# SCH_NIRV2_1_NOMOSFET-REG.net
KiCad netlist of a schematic drawn in EasyEDA
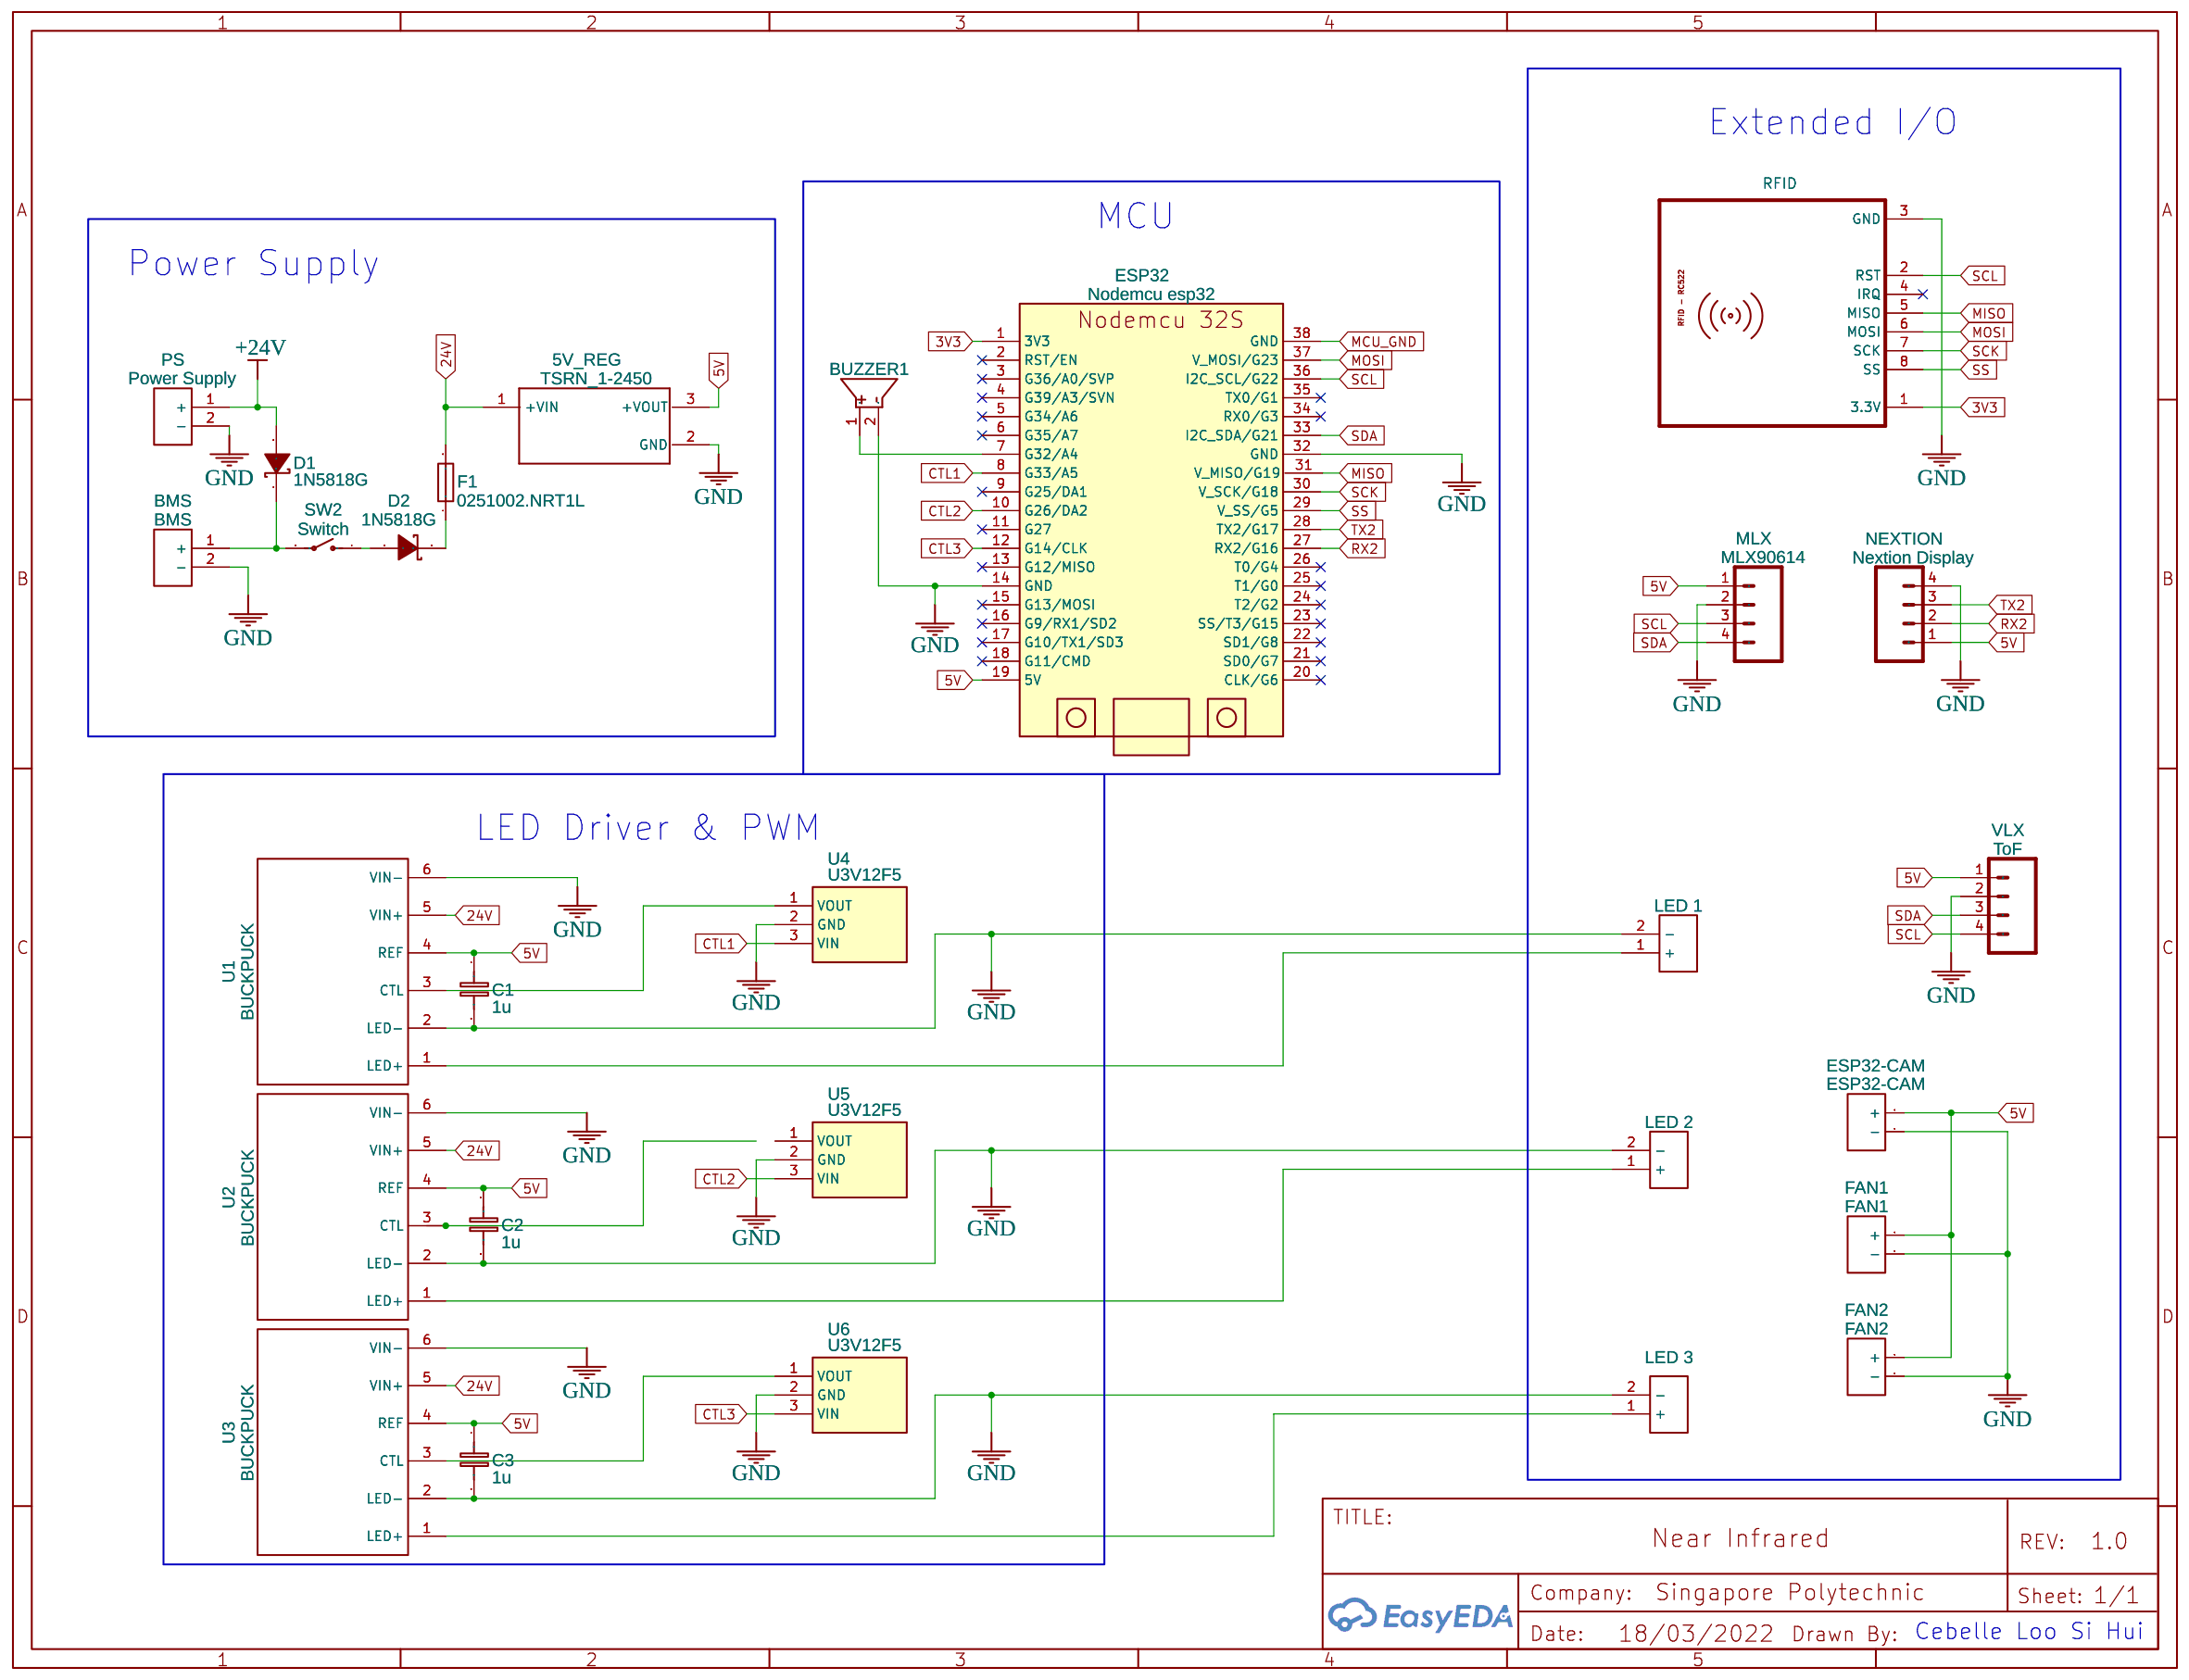
[diagram p0: schematic sheet]

(export (version "E")
  (design (tool "Eeschema 10.0.6"))
  (components
    (comp (ref "5V_REG") (value "TSRN_1-2450") (libsource (lib "") (part "TSRN_1-2450")))
    (comp (ref "BMS")
      (value "BMS")
      (fields
        (field (name "BOM_Manufacturer Part") "WJ103-5.00-2P")
        (field (name "BOM_Supplier Part") "C8439")
      )
      (libsource (lib "") (part "WJ103-5.00-2P_1"))
    )
    (comp (ref "BUZZER1")
      (value "FMQ-BUZZER2")
      (fields (field (name "BOM_Supplier Part") "C9900006103"))
      (libsource (lib "") (part "FMQ-BUZZER2"))
    )
    (comp (ref "C1") (value "1u") (libsource (lib "") (part "CAP-C")))
    (comp (ref "C2") (value "1u") (libsource (lib "") (part "CAP-C")))
    (comp (ref "C3") (value "1u") (libsource (lib "") (part "CAP-C_1")))
    (comp (ref "D1")
      (value "1N5818G")
      (fields (field (name "BOM_Supplier Part") "C232462"))
      (libsource (lib "") (part "1N5818G"))
    )
    (comp (ref "D2")
      (value "1N5818G")
      (fields (field (name "BOM_Supplier Part") "C232462"))
      (libsource (lib "") (part "1N5818G_1"))
    )
    (comp (ref "ESP32") (value "Nodemcu esp32") (libsource (lib "") (part "Nodemcu esp32")))
    (comp (ref "ESP32-CAM")
      (value "ESP32-CAM")
      (fields
        (field (name "BOM_Manufacturer Part") "2.54-1*2PFemale")
        (field (name "BOM_Supplier Part") "C49661")
      )
      (libsource (lib "") (part "Header-Female-2.54_1x2_1"))
    )
    (comp (ref "F1")
      (value "0251002.NRT1L")
      (fields (field (name "BOM_Supplier Part") "C151088"))
      (libsource (lib "") (part "0251002.NRT1L"))
    )
    (comp (ref "FAN1")
      (value "FAN1")
      (fields
        (field (name "BOM_Manufacturer Part") "2.54-1*2PFemale")
        (field (name "BOM_Supplier Part") "C49661")
      )
      (libsource (lib "") (part "Header-Female-2.54_1x2"))
    )
    (comp (ref "FAN2")
      (value "FAN2")
      (fields
        (field (name "BOM_Manufacturer Part") "2.54-1*2PFemale")
        (field (name "BOM_Supplier Part") "C49661")
      )
      (libsource (lib "") (part "Header-Female-2.54_1x2"))
    )
    (comp (ref "LED4")
      (value "LED 1")
      (fields
        (field (name "BOM_Manufacturer Part") "WJ103-5.00-2P")
        (field (name "BOM_Supplier Part") "C8439")
      )
      (libsource (lib "") (part "WJ103-5.00-2P"))
    )
    (comp (ref "LED5")
      (value "LED 2")
      (fields
        (field (name "BOM_Manufacturer Part") "WJ103-5.00-2P")
        (field (name "BOM_Supplier Part") "C8439")
      )
      (libsource (lib "") (part "WJ103-5.00-2P"))
    )
    (comp (ref "LED6")
      (value "LED 3")
      (fields
        (field (name "BOM_Manufacturer Part") "WJ103-5.00-2P")
        (field (name "BOM_Supplier Part") "C8439")
      )
      (libsource (lib "") (part "WJ103-5.00-2P"))
    )
    (comp (ref "MLX") (value "MLX90614") (libsource (lib "") (part "M04POLAR")))
    (comp (ref "NEXTION") (value "Nextion Display") (libsource (lib "") (part "M04POLAR_2")))
    (comp (ref "PS")
      (value "Power Supply")
      (fields
        (field (name "BOM_Manufacturer Part") "WJ103-5.00-2P")
        (field (name "BOM_Supplier Part") "C8439")
      )
      (libsource (lib "") (part "WJ103-5.00-2P_2"))
    )
    (comp (ref "RFID") (value "NO") (libsource (lib "") (part "Unknown_944_-720")))
    (comp (ref "SW2")
      (value "Switch")
      (fields (field (name "BOM_Manufacturer Part") "KCD1-11-1.5x1cm"))
      (libsource (lib "") (part "SWITCH-2P-SPST-Rocker-10x15mm"))
    )
    (comp (ref "U1") (value "BUCKPUCK") (libsource (lib "") (part "BUCKPUCK")))
    (comp (ref "U2") (value "BUCKPUCK") (libsource (lib "") (part "BUCKPUCK")))
    (comp (ref "U3") (value "BUCKPUCK") (libsource (lib "") (part "BUCKPUCK")))
    (comp (ref "U4") (value "U3V12F5") (libsource (lib "") (part "U3V12F5")))
    (comp (ref "U5") (value "U3V12F5") (libsource (lib "") (part "U3V12F5")))
    (comp (ref "U6") (value "U3V12F5") (libsource (lib "") (part "U3V12F5")))
    (comp (ref "VLX") (value "ToF") (libsource (lib "") (part "M04POLAR_1")))
  )
  (nets
    (net (code "1") (name "+24V") (class "Default")
      (node (ref "D1") (pin "2") (pinfunction "A_2") (pintype "unspecified"))
      (node (ref "PS") (pin "1") (pinfunction "+_1") (pintype "unspecified"))
    )
    (net (code "2") (name "3V3") (class "Default")
      (node (ref "ESP32") (pin "1") (pinfunction "3V3_1") (pintype "passive"))
      (node (ref "RFID") (pin "1") (pinfunction "3.3V_1") (pintype "unspecified"))
    )
    (net (code "3") (name "5V") (class "Default")
      (node (ref "5V_REG") (pin "3") (pinfunction "+VOUT_3") (pintype "bidirectional"))
      (node (ref "C1") (pin "1") (pinfunction "1_1") (pintype "unspecified"))
      (node (ref "C2") (pin "1") (pinfunction "1_1") (pintype "unspecified"))
      (node (ref "C3") (pin "1") (pinfunction "1_1") (pintype "unspecified"))
      (node (ref "ESP32") (pin "19") (pinfunction "5V_19") (pintype "passive"))
      (node (ref "ESP32-CAM") (pin "2") (pinfunction "+_2") (pintype "input"))
      (node (ref "FAN1") (pin "2") (pinfunction "+_2") (pintype "input"))
      (node (ref "FAN2") (pin "2") (pinfunction "+_2") (pintype "input"))
      (node (ref "MLX") (pin "1") (pinfunction "GND_1") (pintype "unspecified"))
      (node (ref "NEXTION") (pin "1") (pinfunction "GND_1") (pintype "unspecified"))
      (node (ref "U1") (pin "4") (pinfunction "REF_4") (pintype "unspecified"))
      (node (ref "U2") (pin "4") (pinfunction "REF_4") (pintype "unspecified"))
      (node (ref "U3") (pin "4") (pinfunction "REF_4") (pintype "unspecified"))
      (node (ref "VLX") (pin "1") (pinfunction "GND_1") (pintype "unspecified"))
    )
    (net (code "4") (name "24V") (class "Default")
      (node (ref "5V_REG") (pin "1") (pinfunction "+VIN_1") (pintype "bidirectional"))
      (node (ref "F1") (pin "2") (pinfunction "2_2") (pintype "unspecified"))
      (node (ref "U1") (pin "5") (pinfunction "VIN+_5") (pintype "unspecified"))
      (node (ref "U2") (pin "5") (pinfunction "VIN+_5") (pintype "unspecified"))
      (node (ref "U3") (pin "5") (pinfunction "VIN+_5") (pintype "unspecified"))
    )
    (net (code "5") (name "CTL1") (class "Default")
      (node (ref "ESP32") (pin "8") (pinfunction "G33/A5_8") (pintype "bidirectional"))
      (node (ref "U4") (pin "3") (pinfunction "VIN_3") (pintype "unspecified"))
    )
    (net (code "6") (name "CTL2") (class "Default")
      (node (ref "ESP32") (pin "10") (pinfunction "G26/DA2_10") (pintype "bidirectional"))
      (node (ref "U5") (pin "3") (pinfunction "VIN_3") (pintype "unspecified"))
    )
    (net (code "7") (name "CTL3") (class "Default")
      (node (ref "ESP32") (pin "12") (pinfunction "G14/CLK_12") (pintype "bidirectional"))
      (node (ref "U6") (pin "3") (pinfunction "VIN_3") (pintype "unspecified"))
    )
    (net (code "8") (name "GND") (class "Default")
      (node (ref "5V_REG") (pin "2") (pinfunction "GND_2") (pintype "bidirectional"))
      (node (ref "BMS") (pin "2") (pinfunction "-_2") (pintype "unspecified"))
      (node (ref "BUZZER1") (pin "2") (pinfunction "2_2") (pintype "unspecified"))
      (node (ref "C1") (pin "2") (pinfunction "2_2") (pintype "unspecified"))
      (node (ref "C2") (pin "2") (pinfunction "2_2") (pintype "unspecified"))
      (node (ref "C3") (pin "2") (pinfunction "2_2") (pintype "unspecified"))
      (node (ref "ESP32") (pin "14") (pinfunction "GND_14") (pintype "passive"))
      (node (ref "ESP32") (pin "32") (pinfunction "GND_32") (pintype "passive"))
      (node (ref "ESP32-CAM") (pin "1") (pinfunction "-_1") (pintype "input"))
      (node (ref "FAN1") (pin "1") (pinfunction "-_1") (pintype "input"))
      (node (ref "FAN2") (pin "1") (pinfunction "-_1") (pintype "input"))
      (node (ref "LED4") (pin "2") (pinfunction "-_2") (pintype "unspecified"))
      (node (ref "LED5") (pin "2") (pinfunction "-_2") (pintype "unspecified"))
      (node (ref "LED6") (pin "2") (pinfunction "-_2") (pintype "unspecified"))
      (node (ref "MLX") (pin "2") (pinfunction "RX_2") (pintype "unspecified"))
      (node (ref "NEXTION") (pin "4") (pinfunction "+5V_4") (pintype "unspecified"))
      (node (ref "PS") (pin "2") (pinfunction "-_2") (pintype "unspecified"))
      (node (ref "RFID") (pin "3") (pinfunction "GND_3") (pintype "unspecified"))
      (node (ref "U1") (pin "2") (pinfunction "LED-_2") (pintype "unspecified"))
      (node (ref "U1") (pin "6") (pinfunction "VIN-_6") (pintype "unspecified"))
      (node (ref "U2") (pin "2") (pinfunction "LED-_2") (pintype "unspecified"))
      (node (ref "U2") (pin "6") (pinfunction "VIN-_6") (pintype "unspecified"))
      (node (ref "U3") (pin "2") (pinfunction "LED-_2") (pintype "unspecified"))
      (node (ref "U3") (pin "6") (pinfunction "VIN-_6") (pintype "unspecified"))
      (node (ref "U4") (pin "2") (pinfunction "GND_2") (pintype "unspecified"))
      (node (ref "U5") (pin "2") (pinfunction "GND_2") (pintype "unspecified"))
      (node (ref "U6") (pin "2") (pinfunction "GND_2") (pintype "unspecified"))
      (node (ref "VLX") (pin "2") (pinfunction "RX_2") (pintype "unspecified"))
    )
    (net (code "9") (name "MCU_GND") (class "Default")
      (node (ref "ESP32") (pin "38") (pinfunction "GND_38") (pintype "passive"))
    )
    (net (code "10") (name "MISO") (class "Default")
      (node (ref "ESP32") (pin "31") (pinfunction "V_MISO/G19_31") (pintype "bidirectional"))
      (node (ref "RFID") (pin "5") (pinfunction "MISO_5") (pintype "unspecified"))
    )
    (net (code "11") (name "MOSI") (class "Default")
      (node (ref "ESP32") (pin "37") (pinfunction "V_MOSI/G23_37") (pintype "bidirectional"))
      (node (ref "RFID") (pin "6") (pinfunction "MOSI_6") (pintype "unspecified"))
    )
    (net (code "12") (name "Net-(BMS-+)") (class "Default")
      (node (ref "BMS") (pin "1") (pinfunction "+_1") (pintype "unspecified"))
      (node (ref "D1") (pin "1") (pinfunction "C_1") (pintype "unspecified"))
      (node (ref "SW2") (pin "2") (pinfunction "P_2") (pintype "unspecified"))
    )
    (net (code "13") (name "Net-(D2-A)") (class "Default")
      (node (ref "D2") (pin "2") (pinfunction "A_2") (pintype "unspecified"))
      (node (ref "SW2") (pin "1") (pinfunction "O_1") (pintype "unspecified"))
    )
    (net (code "14") (name "Net-(D2-C)") (class "Default")
      (node (ref "D2") (pin "1") (pinfunction "C_1") (pintype "unspecified"))
      (node (ref "F1") (pin "1") (pinfunction "1_1") (pintype "unspecified"))
    )
    (net (code "15") (name "Net-(ESP32-G32{slash}A4)") (class "Default")
      (node (ref "BUZZER1") (pin "1") (pinfunction "1_1") (pintype "unspecified"))
      (node (ref "ESP32") (pin "7") (pinfunction "G32/A4_7") (pintype "bidirectional"))
    )
    (net (code "16") (name "Net-(LED4-+)") (class "Default")
      (node (ref "LED4") (pin "1") (pinfunction "+_1") (pintype "unspecified"))
      (node (ref "U1") (pin "1") (pinfunction "LED+_1") (pintype "unspecified"))
    )
    (net (code "17") (name "Net-(LED5-+)") (class "Default")
      (node (ref "LED5") (pin "1") (pinfunction "+_1") (pintype "unspecified"))
      (node (ref "U2") (pin "1") (pinfunction "LED+_1") (pintype "unspecified"))
    )
    (net (code "18") (name "Net-(LED6-+)") (class "Default")
      (node (ref "LED6") (pin "1") (pinfunction "+_1") (pintype "unspecified"))
      (node (ref "U3") (pin "1") (pinfunction "LED+_1") (pintype "unspecified"))
    )
    (net (code "19") (name "Net-(U1-CTL)") (class "Default")
      (node (ref "U1") (pin "3") (pinfunction "CTL_3") (pintype "unspecified"))
      (node (ref "U4") (pin "1") (pinfunction "VOUT_1") (pintype "unspecified"))
    )
    (net (code "20") (name "Net-(U3-CTL)") (class "Default")
      (node (ref "U3") (pin "3") (pinfunction "CTL_3") (pintype "unspecified"))
      (node (ref "U6") (pin "1") (pinfunction "VOUT_1") (pintype "unspecified"))
    )
    (net (code "21") (name "RX2") (class "Default")
      (node (ref "ESP32") (pin "27") (pinfunction "RX2/G16_27") (pintype "bidirectional"))
      (node (ref "NEXTION") (pin "2") (pinfunction "RX_2") (pintype "unspecified"))
    )
    (net (code "22") (name "SCK") (class "Default")
      (node (ref "ESP32") (pin "30") (pinfunction "V_SCK/G18_30") (pintype "bidirectional"))
      (node (ref "RFID") (pin "7") (pinfunction "SCK_7") (pintype "unspecified"))
    )
    (net (code "23") (name "SCL") (class "Default")
      (node (ref "ESP32") (pin "36") (pinfunction "I2C_SCL/G22_36") (pintype "bidirectional"))
      (node (ref "MLX") (pin "3") (pinfunction "TX_3") (pintype "unspecified"))
      (node (ref "RFID") (pin "2") (pinfunction "RST_2") (pintype "unspecified"))
      (node (ref "VLX") (pin "4") (pinfunction "+5V_4") (pintype "unspecified"))
    )
    (net (code "24") (name "SDA") (class "Default")
      (node (ref "ESP32") (pin "33") (pinfunction "I2C_SDA/G21_33") (pintype "bidirectional"))
      (node (ref "MLX") (pin "4") (pinfunction "+5V_4") (pintype "unspecified"))
      (node (ref "VLX") (pin "3") (pinfunction "TX_3") (pintype "unspecified"))
    )
    (net (code "25") (name "SS") (class "Default")
      (node (ref "ESP32") (pin "29") (pinfunction "V_SS/G5_29") (pintype "bidirectional"))
      (node (ref "RFID") (pin "8") (pinfunction "SS_8") (pintype "unspecified"))
    )
    (net (code "26") (name "TX2") (class "Default")
      (node (ref "ESP32") (pin "28") (pinfunction "TX2/G17_28") (pintype "bidirectional"))
      (node (ref "NEXTION") (pin "3") (pinfunction "TX_3") (pintype "unspecified"))
    )
    (net (code "27") (name "unconnected-(ESP32-CLK{slash}G6-Pad20)") (class "Default")
      (node (ref "ESP32") (pin "20") (pinfunction "CLK/G6_20") (pintype "bidirectional+no_connect"))
    )
    (net (code "28") (name "unconnected-(ESP32-G9{slash}RX1{slash}SD2-Pad16)") (class "Default")
      (node (ref "ESP32") (pin "16") (pinfunction "G9/RX1/SD2_16") (pintype "bidirectional+no_connect"))
    )
    (net (code "29") (name "unconnected-(ESP32-G10{slash}TX1{slash}SD3-Pad17)") (class "Default")
      (node (ref "ESP32") (pin "17") (pinfunction "G10/TX1/SD3_17") (pintype "bidirectional+no_connect"))
    )
    (net (code "30") (name "unconnected-(ESP32-G11{slash}CMD-Pad18)") (class "Default")
      (node (ref "ESP32") (pin "18") (pinfunction "G11/CMD_18") (pintype "bidirectional+no_connect"))
    )
    (net (code "31") (name "unconnected-(ESP32-G12{slash}MISO-Pad13)") (class "Default")
      (node (ref "ESP32") (pin "13") (pinfunction "G12/MISO_13") (pintype "bidirectional+no_connect"))
    )
    (net (code "32") (name "unconnected-(ESP32-G13{slash}MOSI-Pad15)") (class "Default")
      (node (ref "ESP32") (pin "15") (pinfunction "G13/MOSI_15") (pintype "bidirectional+no_connect"))
    )
    (net (code "33") (name "unconnected-(ESP32-G25{slash}DA1-Pad9)") (class "Default")
      (node (ref "ESP32") (pin "9") (pinfunction "G25/DA1_9") (pintype "bidirectional+no_connect"))
    )
    (net (code "34") (name "unconnected-(ESP32-G27-Pad11)") (class "Default")
      (node (ref "ESP32") (pin "11") (pinfunction "G27_11") (pintype "bidirectional+no_connect"))
    )
    (net (code "35") (name "unconnected-(ESP32-G34{slash}A6-Pad5)") (class "Default")
      (node (ref "ESP32") (pin "5") (pinfunction "G34/A6_5") (pintype "bidirectional+no_connect"))
    )
    (net (code "36") (name "unconnected-(ESP32-G35{slash}A7-Pad6)") (class "Default")
      (node (ref "ESP32") (pin "6") (pinfunction "G35/A7_6") (pintype "bidirectional+no_connect"))
    )
    (net (code "37") (name "unconnected-(ESP32-G36{slash}A0{slash}SVP-Pad3)") (class "Default")
      (node (ref "ESP32") (pin "3") (pinfunction "G36/A0/SVP_3") (pintype "bidirectional+no_connect"))
    )
    (net (code "38") (name "unconnected-(ESP32-G39{slash}A3{slash}SVN-Pad4)") (class "Default")
      (node (ref "ESP32") (pin "4") (pinfunction "G39/A3/SVN_4") (pintype "bidirectional+no_connect"))
    )
    (net (code "39") (name "unconnected-(ESP32-RST{slash}EN-Pad2)") (class "Default")
      (node (ref "ESP32") (pin "2") (pinfunction "RST/EN_2") (pintype "bidirectional+no_connect"))
    )
    (net (code "40") (name "unconnected-(ESP32-RX0{slash}G3-Pad34)") (class "Default")
      (node (ref "ESP32") (pin "34") (pinfunction "RX0/G3_34") (pintype "bidirectional+no_connect"))
    )
    (net (code "41") (name "unconnected-(ESP32-SD0{slash}G7-Pad21)") (class "Default")
      (node (ref "ESP32") (pin "21") (pinfunction "SD0/G7_21") (pintype "bidirectional+no_connect"))
    )
    (net (code "42") (name "unconnected-(ESP32-SD1{slash}G8-Pad22)") (class "Default")
      (node (ref "ESP32") (pin "22") (pinfunction "SD1/G8_22") (pintype "bidirectional+no_connect"))
    )
    (net (code "43") (name "unconnected-(ESP32-SS{slash}T3{slash}G15-Pad23)") (class "Default")
      (node (ref "ESP32") (pin "23") (pinfunction "SS/T3/G15_23") (pintype "bidirectional+no_connect"))
    )
    (net (code "44") (name "unconnected-(ESP32-T0{slash}G4-Pad26)") (class "Default")
      (node (ref "ESP32") (pin "26") (pinfunction "T0/G4_26") (pintype "bidirectional+no_connect"))
    )
    (net (code "45") (name "unconnected-(ESP32-T1{slash}G0-Pad25)") (class "Default")
      (node (ref "ESP32") (pin "25") (pinfunction "T1/G0_25") (pintype "bidirectional+no_connect"))
    )
    (net (code "46") (name "unconnected-(ESP32-T2{slash}G2-Pad24)") (class "Default")
      (node (ref "ESP32") (pin "24") (pinfunction "T2/G2_24") (pintype "bidirectional+no_connect"))
    )
    (net (code "47") (name "unconnected-(ESP32-TX0{slash}G1-Pad35)") (class "Default")
      (node (ref "ESP32") (pin "35") (pinfunction "TX0/G1_35") (pintype "bidirectional+no_connect"))
    )
    (net (code "48") (name "unconnected-(RFID-IRQ-Pad4)") (class "Default")
      (node (ref "RFID") (pin "4") (pinfunction "IRQ_4") (pintype "unspecified+no_connect"))
    )
    (net (code "49") (name "unconnected-(U2-CTL-Pad3)") (class "Default")
      (node (ref "U2") (pin "3") (pinfunction "CTL_3") (pintype "unspecified"))
    )
    (net (code "50") (name "unconnected-(U5-VOUT-Pad1)") (class "Default")
      (node (ref "U5") (pin "1") (pinfunction "VOUT_1") (pintype "unspecified"))
    )
  )
)
